# SCH_Hackercard_2024-08-05.net
KiCad netlist of a schematic drawn in EasyEDA
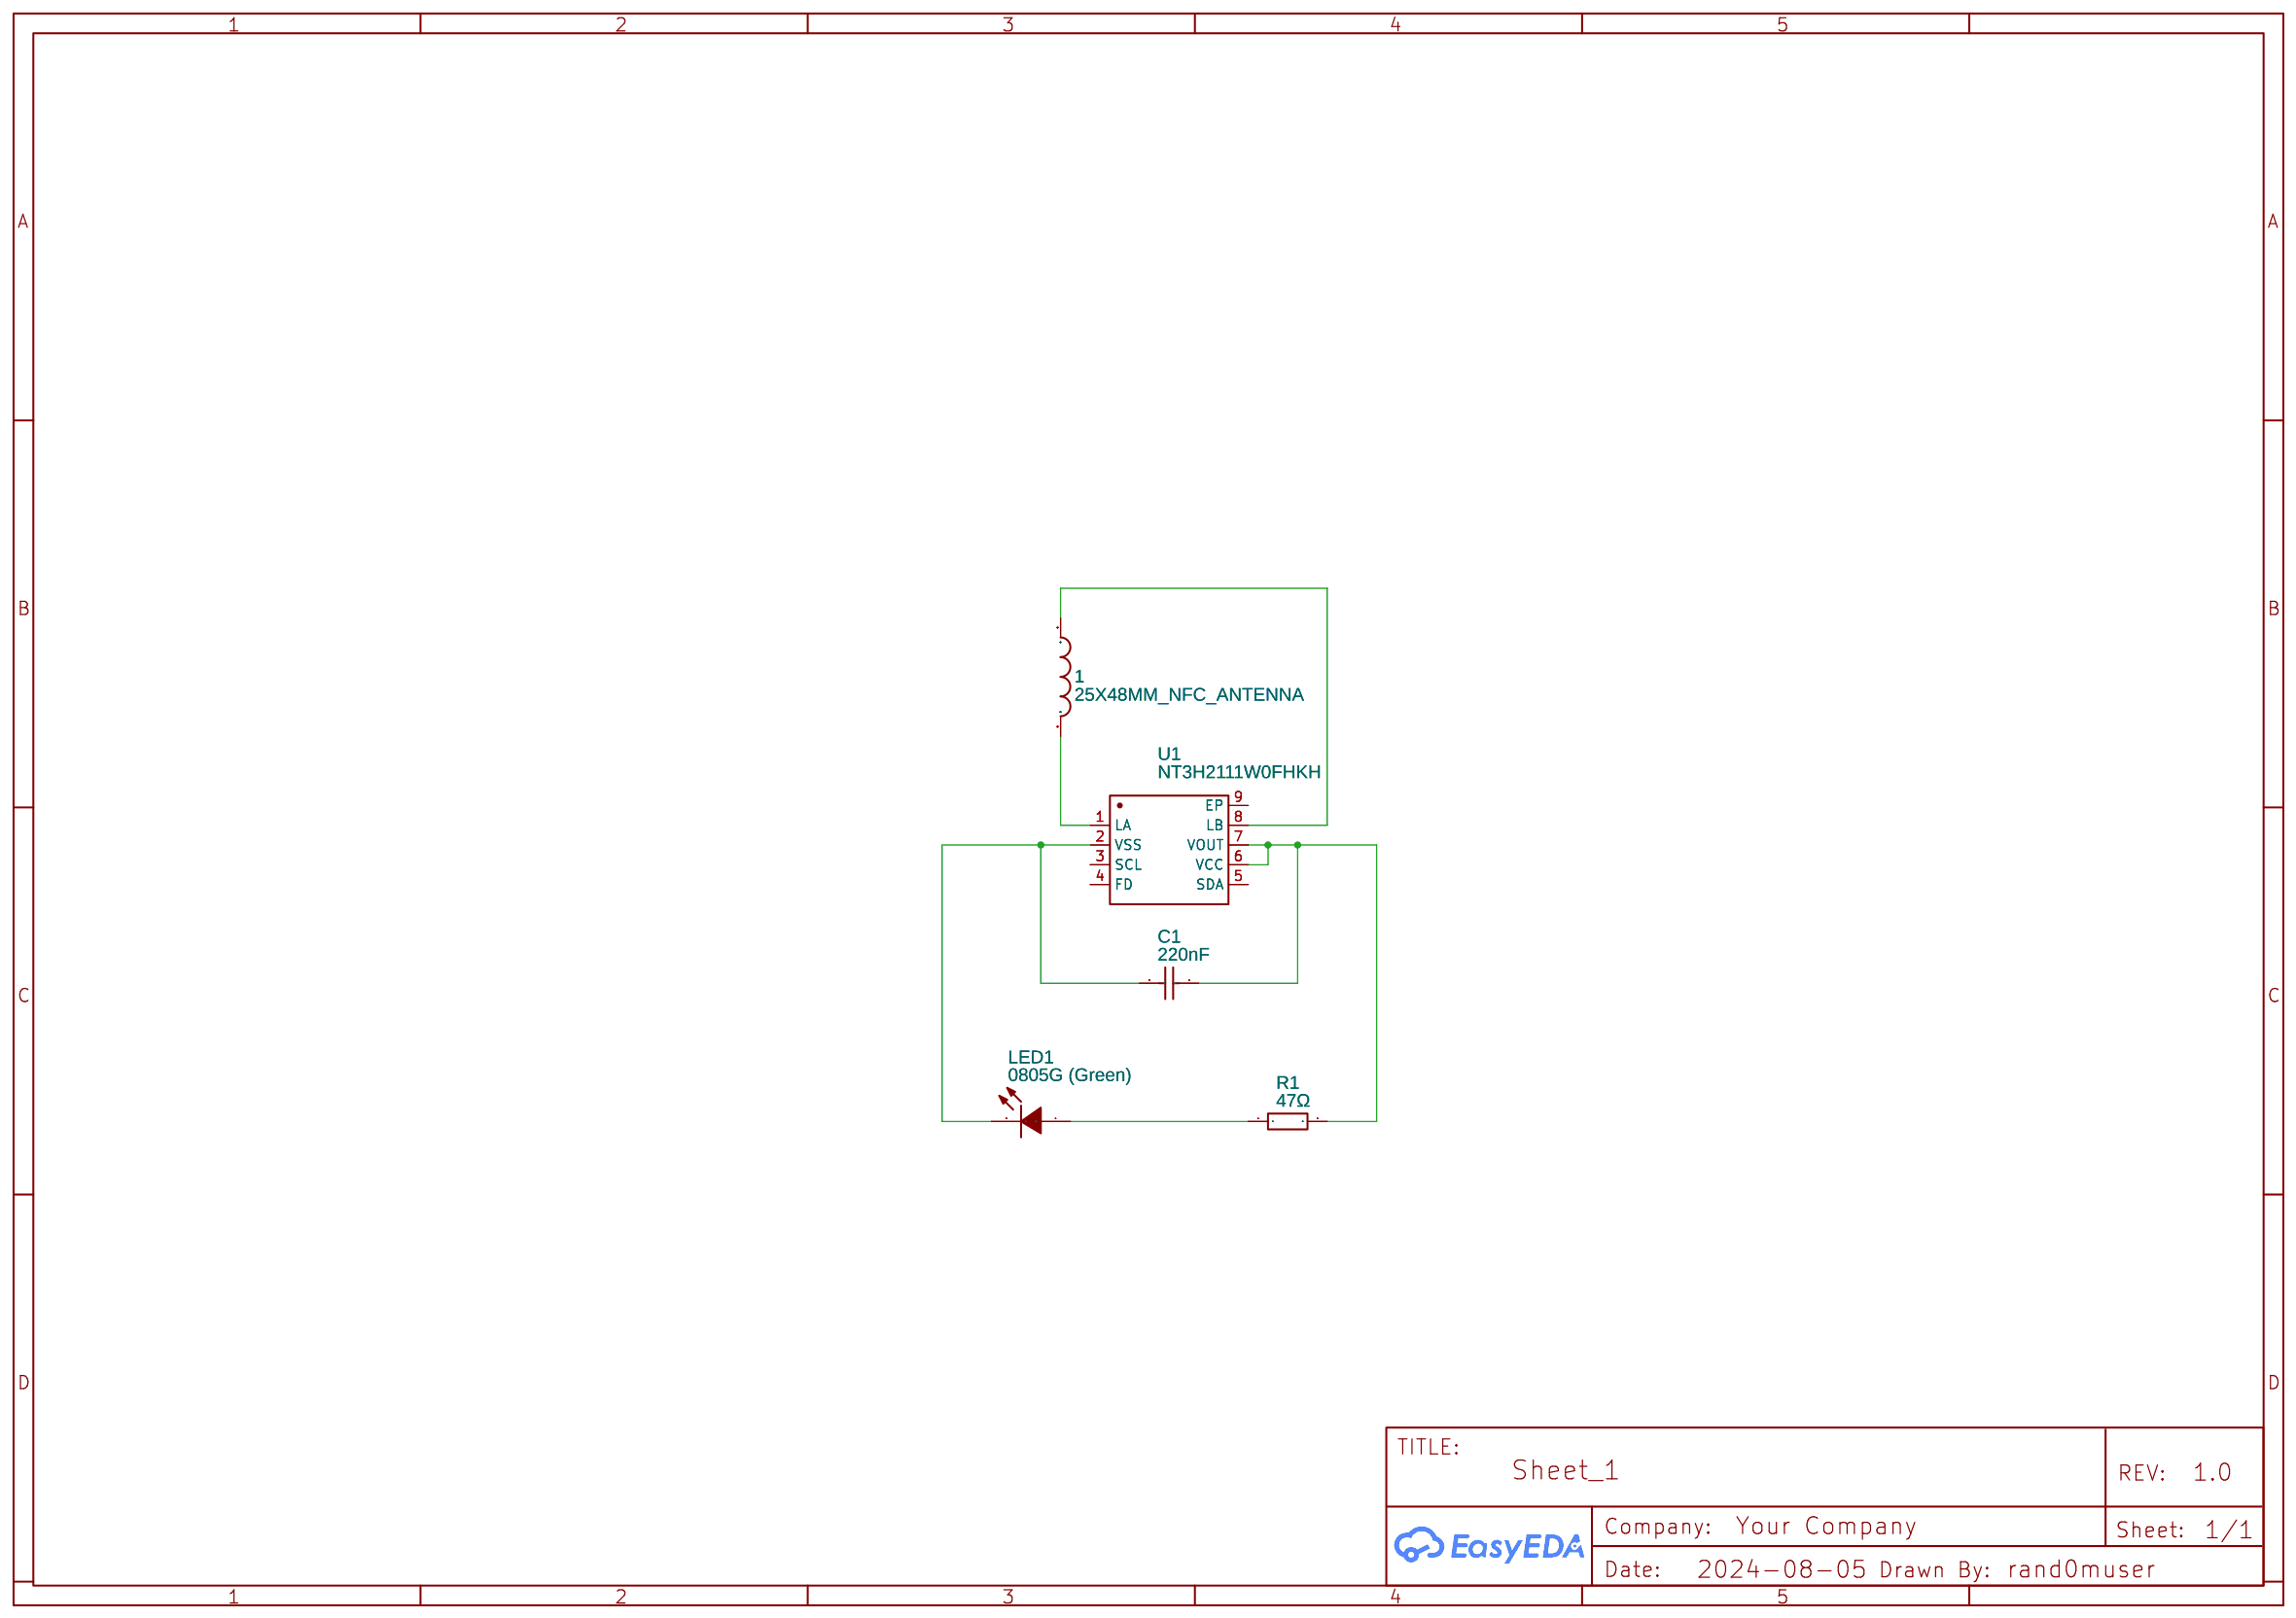
[diagram p0: schematic sheet]

(export (version "E")
  (design (tool "Eeschema 10.0.6"))
  (components
    (comp (ref "1") (value "25X48MM_NFC_ANTENNA") (libsource (lib "") (part "25X48MM_NFC_ANTENNA")))
    (comp (ref "C1")
      (value "220nF")
      (fields
        (field (name "Manufacturer Part") "CL10B224KA8NNNC")
        (field (name "Manufacturer") "SAMSUNG(三星)")
      )
      (libsource (lib "") (part "CL10B224KA8NNNC"))
    )
    (comp (ref "LED1")
      (value "0805G (Green)")
      (fields (field (name "Manufacturer Part") "KT-0805G") (field (name "Manufacturer") "KENTO"))
      (libsource (lib "") (part "0805G (Green)"))
    )
    (comp (ref "R1")
      (value "47Ω")
      (fields
        (field (name "Manufacturer Part") "0603WAF470JT5E")
        (field (name "Manufacturer") "UNI-ROYAL(厚声)")
      )
      (libsource (lib "") (part "0603WAF470JT5E"))
    )
    (comp (ref "U1")
      (value "NT3H2111W0FHKH")
      (fields (field (name "Manufacturer") "NXP(恩智浦)"))
      (libsource (lib "") (part "NT3H2111W0FHKH"))
    )
  )
  (nets
    (net (code "1") (name "Net-(LED1-A)") (class "Default")
      (node (ref "LED1") (pin "1") (pinfunction "A_1") (pintype "unspecified"))
      (node (ref "R1") (pin "1") (pinfunction "1_1") (pintype "input"))
    )
    (net (code "2") (name "Net-(LED1-K)") (class "Default")
      (node (ref "C1") (pin "1") (pinfunction "1_1") (pintype "input"))
      (node (ref "LED1") (pin "2") (pinfunction "K_2") (pintype "unspecified"))
      (node (ref "U1") (pin "2") (pinfunction "VSS_2") (pintype "unspecified"))
    )
    (net (code "3") (name "Net-(U1-LA)") (class "Default")
      (node (ref "1") (pin "P$2") (pinfunction "P$2_P$2") (pintype "bidirectional"))
      (node (ref "U1") (pin "1") (pinfunction "LA_1") (pintype "unspecified"))
    )
    (net (code "4") (name "Net-(U1-LB)") (class "Default")
      (node (ref "1") (pin "P$1") (pinfunction "P$1_P$1") (pintype "bidirectional"))
      (node (ref "U1") (pin "8") (pinfunction "LB_8") (pintype "unspecified"))
    )
    (net (code "5") (name "Net-(U1-VCC)") (class "Default")
      (node (ref "C1") (pin "2") (pinfunction "2_2") (pintype "input"))
      (node (ref "R1") (pin "2") (pinfunction "2_2") (pintype "input"))
      (node (ref "U1") (pin "6") (pinfunction "VCC_6") (pintype "unspecified"))
      (node (ref "U1") (pin "7") (pinfunction "VOUT_7") (pintype "unspecified"))
    )
    (net (code "6") (name "unconnected-(U1-EP-Pad9)") (class "Default")
      (node (ref "U1") (pin "9") (pinfunction "EP_9") (pintype "unspecified"))
    )
    (net (code "7") (name "unconnected-(U1-FD-Pad4)") (class "Default")
      (node (ref "U1") (pin "4") (pinfunction "FD_4") (pintype "unspecified"))
    )
    (net (code "8") (name "unconnected-(U1-SCL-Pad3)") (class "Default")
      (node (ref "U1") (pin "3") (pinfunction "SCL_3") (pintype "unspecified"))
    )
    (net (code "9") (name "unconnected-(U1-SDA-Pad5)") (class "Default")
      (node (ref "U1") (pin "5") (pinfunction "SDA_5") (pintype "unspecified"))
    )
  )
)
